# Power_Control.net
KiCad netlist of a schematic drawn in Altium Designer
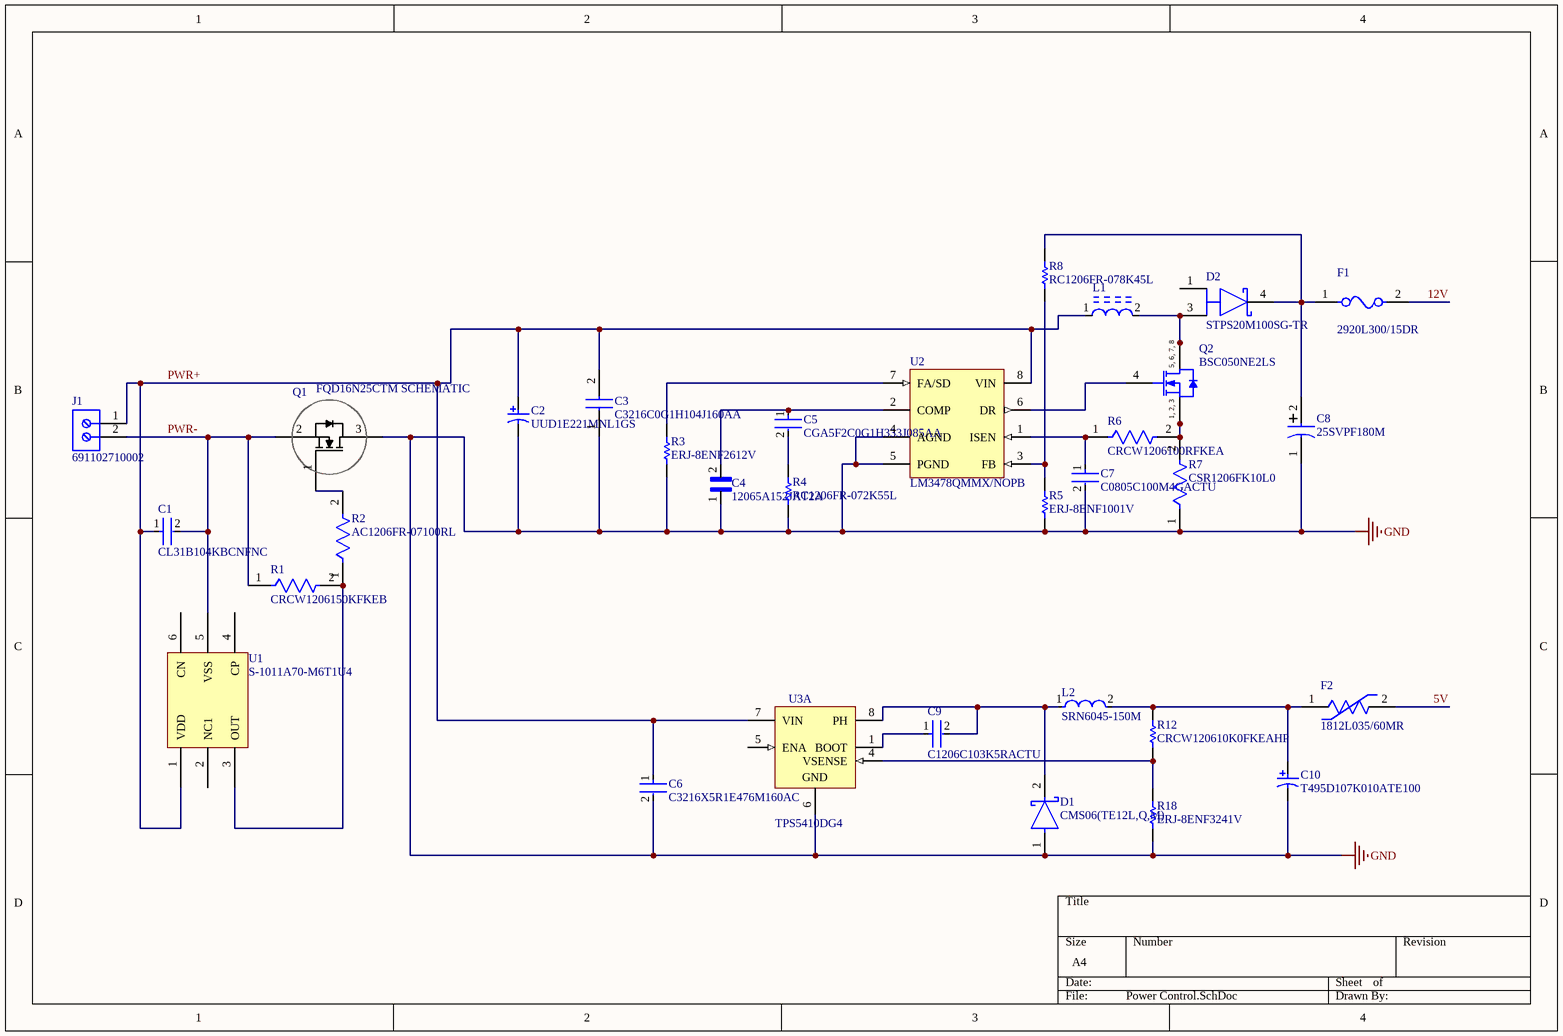
[diagram p0: Power Control.SchDoc]

(export (version "E")
  (design (tool "Eeschema 10.0.6"))
  (components
    (comp (ref "C1")
      (value "CL31B104KBCNFNC")
      (footprint "FP-CL31-IPC_C")
      (description "Cap Ceramic 100nF 50V X7R ±10% SMD 1206 +125°C Embossed T/R")
      (fields (field (name "TOLERANCE") "10%"))
      (libsource (lib "Altium Content Vault") (part "b4654b650e69147ec39a6b967a45e02"))
    )
    (comp (ref "C2")
      (value "UUD1E221MNL1GS")
      (footprint "NIC-CAPA2-8X10_V")
      (fields (field (name "MANUFACTURER") "Nichicon"))
      (libsource (lib "Altium Content Vault") (part "NIC-CAP-P-2"))
    )
    (comp (ref "C3")
      (value "C3216C0G1H104J160AA")
      (footprint "Footprints:C3216_Commercial")
      (description "Capacitor")
      (libsource (lib "*") (part "C3216C0G1H104J160AA"))
    )
    (comp (ref "C4")
      (value "12065A152JAT2A")
      (footprint "CAPC3216X94N")
      (description "1500PF 50V 5% 1206")
      (libsource (lib "12065A152JAT2A") (part "12065A152JAT2A"))
    )
    (comp (ref "C5")
      (value "CGA5F2C0G1H333J085AA")
      (footprint "FP-CGA5L-0_3-0_1-IPC_C")
      (description "Cap Ceramic 33nF 50V C0G 5% Pad SMD 1206 +125°C Automotive T/R")
      (fields (field (name "TOLERANCE") "5%"))
      (libsource (lib "Altium Content Vault") (part "b4654b650e69147ec39a6b967a45e02"))
    )
    (comp (ref "C6")
      (value "C3216X5R1E476M160AC")
      (footprint "FP-C3216-160-MFG")
      (description "CAP CER 47UF 25V X5R 1206")
      (fields (field (name "3DS PART NUMBER") "220-00004") (field (name "VOLTAGE") "25V"))
      (libsource (lib "Altium Content Vault") (part "11868f565c42a9108669ba33697ecf6"))
    )
    (comp (ref "C7")
      (value "C0805C100M4GACTU")
      (footprint "FP-C0805C-DN-MFG")
      (description "CAP CER 10PF 16V 20% NP0 0805")
      (fields
        (field (name "OCTOPART") "https://octopart.com/c0805c100m4gactu-kemet-16430157")
        (field (name "TOLERANCE") "0.2")
      )
      (libsource (lib "Altium Content Vault") (part "b4654b650e69147ec39a6b967a45e02"))
    )
    (comp (ref "C8")
      (value "25SVPF180M")
      (footprint "FCV(8X10.2)")
      (description "Capacitor")
      (fields (field (name "MOUSER2 PART NUMBER") "667-25SVPF180M"))
      (libsource (lib "Unified Library") (part "25SVPF180M"))
    )
    (comp (ref "C9")
      (value "C1206C103K5RACTU")
      (footprint "FP-C1206C-EB-MFG")
      (description "CAP CER 10000PF 50V X7R 1206")
      (fields
        (field (name "OCTOPART") "https://octopart.com/c1206c103k5ractu-kemet-130245")
        (field (name "MANUFACTURER") "KEMET")
      )
      (libsource (lib "Altium Content Vault") (part "b4654b650e69147ec39a6b967a45e02"))
    )
    (comp (ref "C10")
      (value "T495D107K010ATE100")
      (footprint "KEMT-T495-D_L")
      (description "Capacitor, Tantalum, 100 uF, +/- 10%, 10 V, -55 to 125 degC, 2-Pin SMD, RoHS, Tape and Reel")
      (fields (field (name "MANUFACTURER") "Kemet"))
      (libsource (lib "Altium Content Vault") (part "CAP-P-2"))
    )
    (comp (ref "D1")
      (value "CMS06(TE12L,Q,M)")
      (footprint "FP-M-FLAT-MFG")
      (description "DIODE SCHOTTKY 30V 2A MFLAT")
      (libsource (lib "Altium Content Vault") (part "360ad2f4ac25a952324d13796385471"))
    )
    (comp (ref "D2")
      (value "STPS20M100SG-TR")
      (footprint "FP-STPS20M100SG-TR-MFG")
      (description "DIODE SCHOTTKY 100V 20A D2PAK")
      (fields
        (field (name "MANUFACTURER") "STMicroelectronics")
        (field (name "OCTOPART") "https://octopart.com/stps20m100sg-tr-stmicroelectronics-17669033")
      )
      (libsource (lib "Altium Content Vault") (part "51e2ec8066ff851c79fc2400fdb0e37"))
    )
    (comp (ref "F1")
      (value "2920L300/15DR")
      (footprint "FP-2920L-MFG")
      (description "PTC RESET FUSE 15V 3A 2920")
      (fields
        (field (name "MANUFACTURER") "Littelfuse")
        (field (name "OCTOPART") "https://octopart.com/2920l300%2F15dr-littelfuse-673797")
      )
      (libsource (lib "Altium Content Vault") (part "5bcf9b9f640e542cf0359d10258e979"))
    )
    (comp (ref "F2")
      (value "1812L035/60MR")
      (footprint "FP-1812L035-60MR-MFG")
      (description "PTC RESET FUSE 60V 350MA 1812")
      (fields
        (field (name "OCTOPART") "https://octopart.com/1812l035%2F60mr-littelfuse-75250819")
        (field (name "MANUFACTURER") "Littelfuse")
      )
      (libsource (lib "Altium Content Vault") (part "fdf083d5f6389a9a1c4e51137f46658"))
    )
    (comp (ref "J1")
      (value "691102710002")
      (footprint "691102710002")
      (description "Series 102 - 5.00 mm Horizontal Entry Modular with Pressure Clamp WR-TBL, 2 pin")
      (fields (field (name "MANUFACTURER") "Wurth Elektronik") (field (name "PUBLISHER") "WurthElektronik"))
      (libsource (lib "Altium Content Vault") (part "WE-CN-1P-F-TB2"))
    )
    (comp (ref "L1")
      (value "SRP1250-4R7M")
      (footprint "FP-SRP1250-MFG")
      (description "FIXED IND 4.7UH 12A 15 MOHM SMD")
      (fields (field (name "TOLERANCE") "20%"))
      (libsource (lib "Altium Content Vault") (part "ef89b5c4428841583c856a1aa8e8653"))
    )
    (comp (ref "L2")
      (value "SRN6045-150M")
      (footprint "FP-SRN6045-MFG")
      (description "FIXED IND 15UH 1.9A 95.8MOHM SMD")
      (fields (field (name "TOLERANCE") "20%"))
      (libsource (lib "Altium Content Vault") (part "725321dda6339637d4d059423bc1c3c"))
    )
    (comp (ref "Q1")
      (value "FQD16N25CTM SCHEMATIC")
      (footprint "FQD16N25CTM")
      (libsource (lib "Unified Library") (part "FQD16N25CTM SCHEMATIC"))
    )
    (comp (ref "Q2")
      (value "BSC050NE2LS")
      (footprint "INF-PG-TDSON-8-1_V")
      (description "N-Channel OptiMOS Power-MOSFET, 25 V VDS, 58 A ID, -55 to 150 degC, PG-TDSON-8-1, Reel, Green")
      (fields (field (name "MANUFACTURER") "Infineon"))
      (libsource (lib "Altium Content Vault") (part "INF-NEMOS-SSSGDDDD-8"))
    )
    (comp (ref "R1")
      (value "CRCW1206150KFKEB")
      (footprint "FP-CRCW1206-e3-IPC_B")
      (description "RES Thick Film, 150kΩ, 1%, 0.25W, 100ppm/°C, 1206")
      (fields (field (name "TOLERANCE") "1%"))
      (libsource (lib "Altium Content Vault") (part "1029c3af85768c4190bb7ad29bc67b5"))
    )
    (comp (ref "R2")
      (value "AC1206FR-07100RL")
      (footprint "FP-AC1206-MFG")
      (description "RES SMD 100 OHM 1% 1/4W 1206")
      (fields
        (field (name "OCTOPART") "https://octopart.com/ac1206fr-07100rl-yageo-30511025")
        (field (name "TOLERANCE") "0.01")
      )
      (libsource (lib "Altium Content Vault") (part "1029c3af85768c4190bb7ad29bc67b5"))
    )
    (comp (ref "R3")
      (value "ERJ-8ENF2612V")
      (footprint "RESC3216X70X50LL05T20")
      (fields (field (name "MANUFACTURER") "Panasonic"))
      (libsource (lib "Altium Content Vault") (part "RES"))
    )
    (comp (ref "R4")
      (value "RC1206FR-072K55L")
      (footprint "RESC3116X65X40ML10T20")
      (fields (field (name "MANUFACTURER") "Yageo"))
      (libsource (lib "Altium Content Vault") (part "RES"))
    )
    (comp (ref "R5")
      (value "ERJ-8ENF1001V")
      (footprint "RESC3216X70X50LL05T20")
      (fields (field (name "MANUFACTURER") "Panasonic"))
      (libsource (lib "Altium Content Vault") (part "RES"))
    )
    (comp (ref "R6")
      (value "CRCW1206100RFKEA")
      (footprint "FP-CRCW1206-e3-MFG")
      (description "RES Thick Film, 100Ω, 1%, 0.25W, 100ppm/°C, 1206")
      (fields (field (name "TOLERANCE") "1%"))
      (libsource (lib "Altium Content Vault") (part "1029c3af85768c4190bb7ad29bc67b5"))
    )
    (comp (ref "R7")
      (value "CSR1206FK10L0")
      (footprint "FP-CSR1206-MFG")
      (description "RES 0.01 OHM 1% 1/2W 1206")
      (fields (field (name "TOLERANCE") "1%"))
      (libsource (lib "Altium Content Vault") (part "1029c3af85768c4190bb7ad29bc67b5"))
    )
    (comp (ref "R8")
      (value "RC1206FR-078K45L")
      (footprint "RESC3116X65X40NL10T20")
      (fields (field (name "MANUFACTURER") "Yageo"))
      (libsource (lib "Altium Content Vault") (part "RES"))
    )
    (comp (ref "R12")
      (value "CRCW120610K0FKEAHP")
      (footprint "RESC3116X65X50NL20T20")
      (fields (field (name "MANUFACTURER") "Vishay Dale"))
      (libsource (lib "Altium Content Vault") (part "RES"))
    )
    (comp (ref "R18")
      (value "ERJ-8ENF3241V")
      (footprint "RESC3216X70X50LL05T20")
      (fields (field (name "MANUFACTURER") "Panasonic"))
      (libsource (lib "Altium Content Vault") (part "RES"))
    )
    (comp (ref "U1")
      (value "S-1011A70-M6T1U4")
      (footprint "S-1011A70-M6T1U4")
      (libsource (lib "Unified Library") (part "S-1011A70-M6T1U4"))
    )
    (comp (ref "U2")
      (value "LM3478QMMX/NOPB")
      (footprint "DGK0008A_N")
      (fields (field (name "MANUFACTURER") "Texas Instruments"))
      (libsource (lib "Altium Content Vault") (part "PM-SWREG-LM3478-8"))
    )
    (comp (ref "U3")
      (value "TPS5410DG4")
      (footprint "D8_L")
      (fields (field (name "MANUFACTURER") "Texas Instruments"))
      (libsource (lib "Altium Content Vault") (part "TI-TPS5410D8"))
    )
  )
  (nets
    (net (code "1") (name "/5V") (class "Default")
      (node (ref "F2") (pin "2") (pinfunction "2_2") (pintype "passive"))
    )
    (net (code "2") (name "/12V") (class "Default")
      (node (ref "F1") (pin "2") (pinfunction "2_2") (pintype "passive"))
    )
    (net (code "3") (name "/PWR+") (class "Default")
      (node (ref "C1") (pin "1") (pinfunction "1_1") (pintype "passive"))
      (node (ref "C2") (pin "1") (pinfunction "1_1") (pintype "passive"))
      (node (ref "C3") (pin "2") (pinfunction "2_2") (pintype "passive"))
      (node (ref "C6") (pin "1") (pinfunction "1_1") (pintype "passive"))
      (node (ref "J1") (pin "1") (pinfunction "1_1") (pintype "passive"))
      (node (ref "L1") (pin "1") (pinfunction "1_1") (pintype "passive"))
      (node (ref "U1") (pin "1") (pinfunction "VDD_1") (pintype "passive"))
      (node (ref "U2") (pin "8") (pinfunction "VIN_8") (pintype "power_in"))
      (node (ref "U3") (pin "7") (pinfunction "VIN_7") (pintype "power_in"))
    )
    (net (code "4") (name "/PWR-") (class "Default")
      (node (ref "C1") (pin "2") (pinfunction "2_2") (pintype "passive"))
      (node (ref "J1") (pin "2") (pinfunction "2_2") (pintype "passive"))
      (node (ref "Q1") (pin "2") (pinfunction "22_2") (pintype "passive"))
      (node (ref "R1") (pin "1") (pinfunction "1_1") (pintype "passive"))
      (node (ref "U1") (pin "5") (pinfunction "VSS_5") (pintype "passive"))
    )
    (net (code "5") (name "GND") (class "Default")
      (node (ref "C10") (pin "2") (pinfunction "2_2") (pintype "passive"))
      (node (ref "C2") (pin "2") (pinfunction "2_2") (pintype "passive"))
      (node (ref "C3") (pin "1") (pinfunction "1_1") (pintype "passive"))
      (node (ref "C4") (pin "1") (pinfunction "1_1") (pintype "passive"))
      (node (ref "C6") (pin "2") (pinfunction "2_2") (pintype "passive"))
      (node (ref "C7") (pin "2") (pinfunction "2_2") (pintype "passive"))
      (node (ref "C8") (pin "1") (pinfunction "+_1") (pintype "passive"))
      (node (ref "D1") (pin "1") (pinfunction "A_1") (pintype "passive"))
      (node (ref "Q1") (pin "3") (pinfunction "20_3") (pintype "passive"))
      (node (ref "R18") (pin "1") (pinfunction "1_1") (pintype "passive"))
      (node (ref "R3") (pin "1") (pinfunction "1_1") (pintype "passive"))
      (node (ref "R4") (pin "1") (pinfunction "1_1") (pintype "passive"))
      (node (ref "R5") (pin "1") (pinfunction "1_1") (pintype "passive"))
      (node (ref "R7") (pin "1") (pinfunction "1_1") (pintype "passive"))
      (node (ref "U2") (pin "4") (pinfunction "AGND_4") (pintype "power_in"))
      (node (ref "U2") (pin "5") (pinfunction "PGND_5") (pintype "power_in"))
      (node (ref "U3") (pin "6") (pinfunction "GND_6") (pintype "power_in"))
    )
    (net (code "6") (name "Net-(C5-Pad2)") (class "Default")
      (node (ref "C5") (pin "2") (pinfunction "2_2") (pintype "passive"))
      (node (ref "R4") (pin "2") (pinfunction "2_2") (pintype "passive"))
    )
    (net (code "7") (name "Net-(C8--)") (class "Default")
      (node (ref "C8") (pin "2") (pinfunction "-_2") (pintype "passive"))
      (node (ref "D2") (pin "4") (pinfunction "K_4") (pintype "passive"))
      (node (ref "F1") (pin "1") (pinfunction "1_1") (pintype "passive"))
      (node (ref "R8") (pin "2") (pinfunction "2_2") (pintype "passive"))
    )
    (net (code "8") (name "Net-(C10-Pad1)") (class "Default")
      (node (ref "C10") (pin "1") (pinfunction "1_1") (pintype "passive"))
      (node (ref "F2") (pin "1") (pinfunction "1_1") (pintype "passive"))
      (node (ref "L2") (pin "2") (pinfunction "2_2") (pintype "passive"))
      (node (ref "R12") (pin "2") (pinfunction "2_2") (pintype "passive"))
    )
    (net (code "9") (name "Net-(D1-C)") (class "Default")
      (node (ref "C9") (pin "2") (pinfunction "2_2") (pintype "passive"))
      (node (ref "D1") (pin "2") (pinfunction "C_2") (pintype "passive"))
      (node (ref "L2") (pin "1") (pinfunction "1_1") (pintype "passive"))
      (node (ref "U3") (pin "8") (pinfunction "PH_8") (pintype "power_in"))
    )
    (net (code "10") (name "Net-(D2-A-Pad3)") (class "Default")
      (node (ref "D2") (pin "3") (pinfunction "A_3") (pintype "passive"))
      (node (ref "L1") (pin "2") (pinfunction "2_2") (pintype "passive"))
      (node (ref "Q2") (pin "5") (pinfunction "DRAIN_5") (pintype "passive"))
      (node (ref "Q2") (pin "6") (pinfunction "DRAIN_6") (pintype "passive"))
      (node (ref "Q2") (pin "7") (pinfunction "DRAIN_7") (pintype "passive"))
      (node (ref "Q2") (pin "8") (pinfunction "DRAIN_8") (pintype "passive"))
    )
    (net (code "11") (name "Net-(Q1-21)") (class "Default")
      (node (ref "Q1") (pin "1") (pinfunction "21_1") (pintype "passive"))
      (node (ref "R2") (pin "2") (pinfunction "2_2") (pintype "passive"))
    )
    (net (code "12") (name "Net-(Q2-GATE)") (class "Default")
      (node (ref "Q2") (pin "4") (pinfunction "GATE_4") (pintype "passive"))
      (node (ref "U2") (pin "6") (pinfunction "DR_6") (pintype "output"))
    )
    (net (code "13") (name "Net-(Q2-SOURCE-Pad1)") (class "Default")
      (node (ref "Q2") (pin "1") (pinfunction "SOURCE_1") (pintype "passive"))
      (node (ref "Q2") (pin "2") (pinfunction "SOURCE_2") (pintype "passive"))
      (node (ref "Q2") (pin "3") (pinfunction "SOURCE_3") (pintype "passive"))
      (node (ref "R6") (pin "2") (pinfunction "2_2") (pintype "passive"))
      (node (ref "R7") (pin "2") (pinfunction "2_2") (pintype "passive"))
    )
    (net (code "14") (name "Net-(U1-OUT)") (class "Default")
      (node (ref "R1") (pin "2") (pinfunction "2_2") (pintype "passive"))
      (node (ref "R2") (pin "1") (pinfunction "1_1") (pintype "passive"))
      (node (ref "U1") (pin "3") (pinfunction "OUT_3") (pintype "passive"))
    )
    (net (code "15") (name "Net-(U2-COMP)") (class "Default")
      (node (ref "C4") (pin "2") (pinfunction "2_2") (pintype "passive"))
      (node (ref "C5") (pin "1") (pinfunction "1_1") (pintype "passive"))
      (node (ref "U2") (pin "2") (pinfunction "COMP_2") (pintype "passive"))
    )
    (net (code "16") (name "Net-(U2-FA{slash}SD)") (class "Default")
      (node (ref "R3") (pin "2") (pinfunction "2_2") (pintype "passive"))
      (node (ref "U2") (pin "7") (pinfunction "FA/SD_7") (pintype "input"))
    )
    (net (code "17") (name "Net-(U2-FB)") (class "Default")
      (node (ref "R5") (pin "2") (pinfunction "2_2") (pintype "passive"))
      (node (ref "R8") (pin "1") (pinfunction "1_1") (pintype "passive"))
      (node (ref "U2") (pin "3") (pinfunction "FB_3") (pintype "input"))
    )
    (net (code "18") (name "Net-(U2-ISEN)") (class "Default")
      (node (ref "C7") (pin "1") (pinfunction "1_1") (pintype "passive"))
      (node (ref "R6") (pin "1") (pinfunction "1_1") (pintype "passive"))
      (node (ref "U2") (pin "1") (pinfunction "ISEN_1") (pintype "input"))
    )
    (net (code "19") (name "Net-(U3A-BOOT)") (class "Default")
      (node (ref "C9") (pin "1") (pinfunction "1_1") (pintype "passive"))
      (node (ref "U3") (pin "1") (pinfunction "BOOT_1") (pintype "passive"))
    )
    (net (code "20") (name "Net-(U3A-VSENSE)") (class "Default")
      (node (ref "R12") (pin "1") (pinfunction "1_1") (pintype "passive"))
      (node (ref "R18") (pin "2") (pinfunction "2_2") (pintype "passive"))
      (node (ref "U3") (pin "4") (pinfunction "VSENSE_4") (pintype "input"))
    )
    (net (code "21") (name "unconnected-(D2-A-Pad1)") (class "Default")
      (node (ref "D2") (pin "1") (pinfunction "A_1") (pintype "passive"))
    )
    (net (code "22") (name "unconnected-(U1-CN-Pad6)") (class "Default")
      (node (ref "U1") (pin "6") (pinfunction "CN_6") (pintype "passive"))
    )
    (net (code "23") (name "unconnected-(U1-CP-Pad4)") (class "Default")
      (node (ref "U1") (pin "4") (pinfunction "CP_4") (pintype "passive"))
    )
    (net (code "24") (name "unconnected-(U1-NC1-Pad2)") (class "Default")
      (node (ref "U1") (pin "2") (pinfunction "NC1_2") (pintype "passive"))
    )
    (net (code "25") (name "unconnected-(U3A-ENA-Pad5)") (class "Default")
      (node (ref "U3") (pin "5") (pinfunction "ENA_5") (pintype "input"))
    )
  )
)
